# battery_pack.net
KiCad netlist of a schematic drawn in Altium Designer
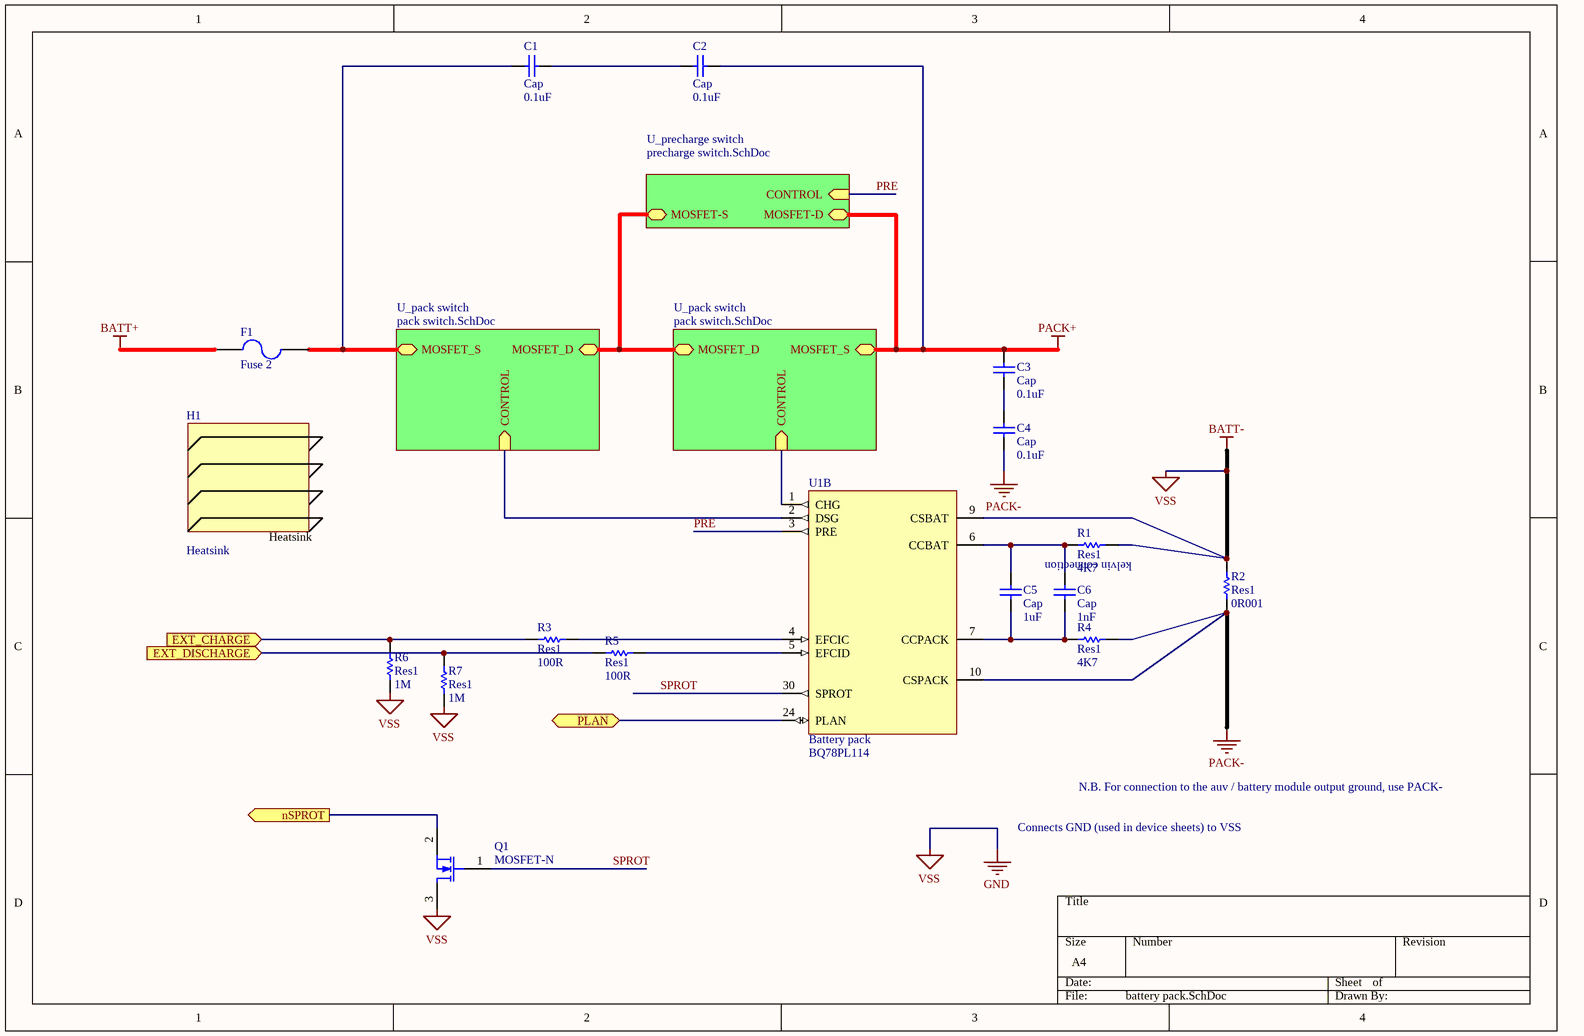
[diagram p0: battery pack.SchDoc]

(export (version "E")
  (design (tool "Eeschema 10.0.6"))
  (components
    (comp (ref "C1")
      (value "Cap")
      (footprint "C0805")
      (description "Capacitor")
      (fields (field (name "ALTIUM_VALUE") "0.1uF") (field (name "PUBLISHER") "Altium Limited"))
      (libsource (lib "Miscellaneous Devices") (part "Cap"))
    )
    (comp (ref "C2")
      (value "Cap")
      (footprint "C0805")
      (description "Capacitor")
      (fields (field (name "ALTIUM_VALUE") "0.1uF") (field (name "PUBLISHER") "Altium Limited"))
      (libsource (lib "Miscellaneous Devices") (part "Cap"))
    )
    (comp (ref "C3")
      (value "Cap")
      (footprint "C0805")
      (description "Capacitor")
      (fields (field (name "ALTIUM_VALUE") "0.1uF") (field (name "PUBLISHER") "Altium Limited"))
      (libsource (lib "Miscellaneous Devices") (part "Cap"))
    )
    (comp (ref "C4")
      (value "Cap")
      (footprint "C0805")
      (description "Capacitor")
      (fields (field (name "ALTIUM_VALUE") "0.1uF") (field (name "PUBLISHER") "Altium Limited"))
      (libsource (lib "Miscellaneous Devices") (part "Cap"))
    )
    (comp (ref "C5")
      (value "Cap")
      (footprint "C0805")
      (description "Capacitor")
      (fields (field (name "ALTIUM_VALUE") "1uF") (field (name "PUBLISHER") "Altium Limited"))
      (libsource (lib "Miscellaneous Devices") (part "Cap"))
    )
    (comp (ref "C6")
      (value "Cap")
      (footprint "C0805")
      (description "Capacitor")
      (fields (field (name "ALTIUM_VALUE") "1nF") (field (name "PUBLISHER") "Altium Limited"))
      (libsource (lib "Miscellaneous Devices") (part "Cap"))
    )
    (comp (ref "F1")
      (value "Fuse 2")
      (footprint "FUSE outline")
      (description "Fuse")
      (fields (field (name "PUBLISHER") "Altium Limited"))
      (libsource (lib "Miscellaneous Devices") (part "Fuse 2"))
    )
    (comp (ref "H1") (value "Heatsink") (libsource (lib "heatsink") (part "Heatsink")))
    (comp (ref "Q1")
      (value "MOSFET-N")
      (footprint "2N7002")
      (description "NXP - 2N7002 - MOSFET,N CH, 60V,0.3A,SOT23")
      (libsource (lib "2N7002") (part "2N7002"))
    )
    (comp (ref "R1")
      (value "Res1")
      (footprint "R0603")
      (description "Resistor")
      (fields (field (name "ALTIUM_VALUE") "4K7") (field (name "PUBLISHER") "Altium Limited"))
      (libsource (lib "Miscellaneous Devices") (part "Res1"))
    )
    (comp (ref "R2")
      (value "Res1")
      (footprint "BCS80R001F")
      (description "BI TECHNOLOGIES BCS80R001F")
      (fields (field (name "ALTIUM_VALUE") "0R001") (field (name "PUBLISHER") "Altium Limited"))
      (libsource (lib "Miscellaneous Devices") (part "Res1"))
    )
    (comp (ref "R3")
      (value "Res1")
      (footprint "R0603")
      (description "Resistor")
      (fields (field (name "ALTIUM_VALUE") "100R") (field (name "PUBLISHER") "Altium Limited"))
      (libsource (lib "Miscellaneous Devices") (part "Res1"))
    )
    (comp (ref "R4")
      (value "Res1")
      (footprint "R0603")
      (description "Resistor")
      (fields (field (name "ALTIUM_VALUE") "4K7") (field (name "PUBLISHER") "Altium Limited"))
      (libsource (lib "Miscellaneous Devices") (part "Res1"))
    )
    (comp (ref "R5")
      (value "Res1")
      (footprint "R0603")
      (description "Resistor")
      (fields (field (name "ALTIUM_VALUE") "100R") (field (name "PUBLISHER") "Altium Limited"))
      (libsource (lib "Miscellaneous Devices") (part "Res1"))
    )
    (comp (ref "R6")
      (value "Res1")
      (footprint "R0603")
      (description "Resistor")
      (fields (field (name "ALTIUM_VALUE") "1M") (field (name "PUBLISHER") "Altium Limited"))
      (libsource (lib "Miscellaneous Devices") (part "Res1"))
    )
    (comp (ref "R7")
      (value "Res1")
      (footprint "R0603")
      (description "Resistor")
      (fields (field (name "ALTIUM_VALUE") "1M") (field (name "PUBLISHER") "Altium Limited"))
      (libsource (lib "Miscellaneous Devices") (part "Res1"))
    )
    (comp (ref "U1")
      (value "BQ78PL114")
      (footprint "QFN50P700X700X100-48N")
      (description "IC, BATT MANAGEMENT CONTRL, 48QFN")
      (libsource (lib "BQ78PL114") (part "BQ78PL114"))
    )
  )
  (nets
    (net (code "1") (name "/CONTROL") (class "Default")
      (node (ref "U1") (pin "1") (pinfunction "CHG_1") (pintype "output"))
    )
    (net (code "2") (name "/CONTROL_1") (class "Default")
      (node (ref "U1") (pin "2") (pinfunction "DSG_2") (pintype "output"))
    )
    (net (code "3") (name "/EXT_CHARGE") (class "Default")
      (node (ref "R3") (pin "1") (pinfunction "1_1") (pintype "passive"))
      (node (ref "R6") (pin "1") (pinfunction "1_1") (pintype "passive"))
    )
    (net (code "4") (name "/EXT_DISCHARGE") (class "Default")
      (node (ref "R5") (pin "1") (pinfunction "1_1") (pintype "passive"))
      (node (ref "R7") (pin "1") (pinfunction "1_1") (pintype "passive"))
    )
    (net (code "6") (name "/MOSFET_S") (class "Default")
      (node (ref "C1") (pin "1") (pinfunction "1_1") (pintype "passive"))
      (node (ref "F1") (pin "1") (pinfunction "1_1") (pintype "passive"))
    )
    (net (code "7") (name "/PLAN") (class "Default")
      (node (ref "U1") (pin "24") (pinfunction "PLAN_24") (pintype "bidirectional"))
    )
    (net (code "8") (name "/PRE") (class "Default")
      (node (ref "U1") (pin "3") (pinfunction "PRE_3") (pintype "output"))
    )
    (net (code "9") (name "/SPROT") (class "Default")
      (node (ref "Q1") (pin "1") (pinfunction "G_1") (pintype "passive"))
      (node (ref "U1") (pin "30") (pinfunction "SPROT_30") (pintype "output"))
    )
    (net (code "10") (name "/nSPROT") (class "Default")
      (node (ref "Q1") (pin "2") (pinfunction "S_2") (pintype "passive"))
    )
    (net (code "11") (name "BATT+") (class "Default")
      (node (ref "F1") (pin "2") (pinfunction "2_2") (pintype "passive"))
    )
    (net (code "12") (name "BATT-") (class "Default")
      (node (ref "Q1") (pin "3") (pinfunction "D_3") (pintype "passive"))
      (node (ref "R1") (pin "2") (pinfunction "2_2") (pintype "passive"))
      (node (ref "R2") (pin "2") (pinfunction "2_2") (pintype "passive"))
      (node (ref "R6") (pin "2") (pinfunction "2_2") (pintype "passive"))
      (node (ref "R7") (pin "2") (pinfunction "2_2") (pintype "passive"))
      (node (ref "U1") (pin "9") (pinfunction "CSBAT_9") (pintype "passive"))
    )
    (net (code "13") (name "Net-(C1-Pad2)") (class "Default")
      (node (ref "C1") (pin "2") (pinfunction "2_2") (pintype "passive"))
      (node (ref "C2") (pin "1") (pinfunction "1_1") (pintype "passive"))
    )
    (net (code "14") (name "Net-(C3-Pad1)") (class "Default")
      (node (ref "C3") (pin "1") (pinfunction "1_1") (pintype "passive"))
      (node (ref "C4") (pin "2") (pinfunction "2_2") (pintype "passive"))
    )
    (net (code "15") (name "Net-(U1B-CCBAT)") (class "Default")
      (node (ref "C5") (pin "2") (pinfunction "2_2") (pintype "passive"))
      (node (ref "C6") (pin "2") (pinfunction "2_2") (pintype "passive"))
      (node (ref "R1") (pin "1") (pinfunction "1_1") (pintype "passive"))
      (node (ref "U1") (pin "6") (pinfunction "CCBAT_6") (pintype "passive"))
    )
    (net (code "16") (name "Net-(U1B-CCPACK)") (class "Default")
      (node (ref "C5") (pin "1") (pinfunction "1_1") (pintype "passive"))
      (node (ref "C6") (pin "1") (pinfunction "1_1") (pintype "passive"))
      (node (ref "R4") (pin "1") (pinfunction "1_1") (pintype "passive"))
      (node (ref "U1") (pin "7") (pinfunction "CCPACK_7") (pintype "passive"))
    )
    (net (code "17") (name "Net-(U1B-EFCIC)") (class "Default")
      (node (ref "R3") (pin "2") (pinfunction "2_2") (pintype "passive"))
      (node (ref "U1") (pin "4") (pinfunction "EFCIC_4") (pintype "input"))
    )
    (net (code "18") (name "Net-(U1B-EFCID)") (class "Default")
      (node (ref "R5") (pin "2") (pinfunction "2_2") (pintype "passive"))
      (node (ref "U1") (pin "5") (pinfunction "EFCID_5") (pintype "input"))
    )
    (net (code "19") (name "PACK+") (class "Default")
      (node (ref "C2") (pin "2") (pinfunction "2_2") (pintype "passive"))
      (node (ref "C3") (pin "2") (pinfunction "2_2") (pintype "passive"))
    )
    (net (code "20") (name "PACK-") (class "Default")
      (node (ref "C4") (pin "1") (pinfunction "1_1") (pintype "passive"))
      (node (ref "R2") (pin "1") (pinfunction "1_1") (pintype "passive"))
      (node (ref "R4") (pin "2") (pinfunction "2_2") (pintype "passive"))
      (node (ref "U1") (pin "10") (pinfunction "CSPACK_10") (pintype "passive"))
    )
  )
)
